# JTAG_Trace.net
KiCad netlist of a schematic drawn in Altium Designer
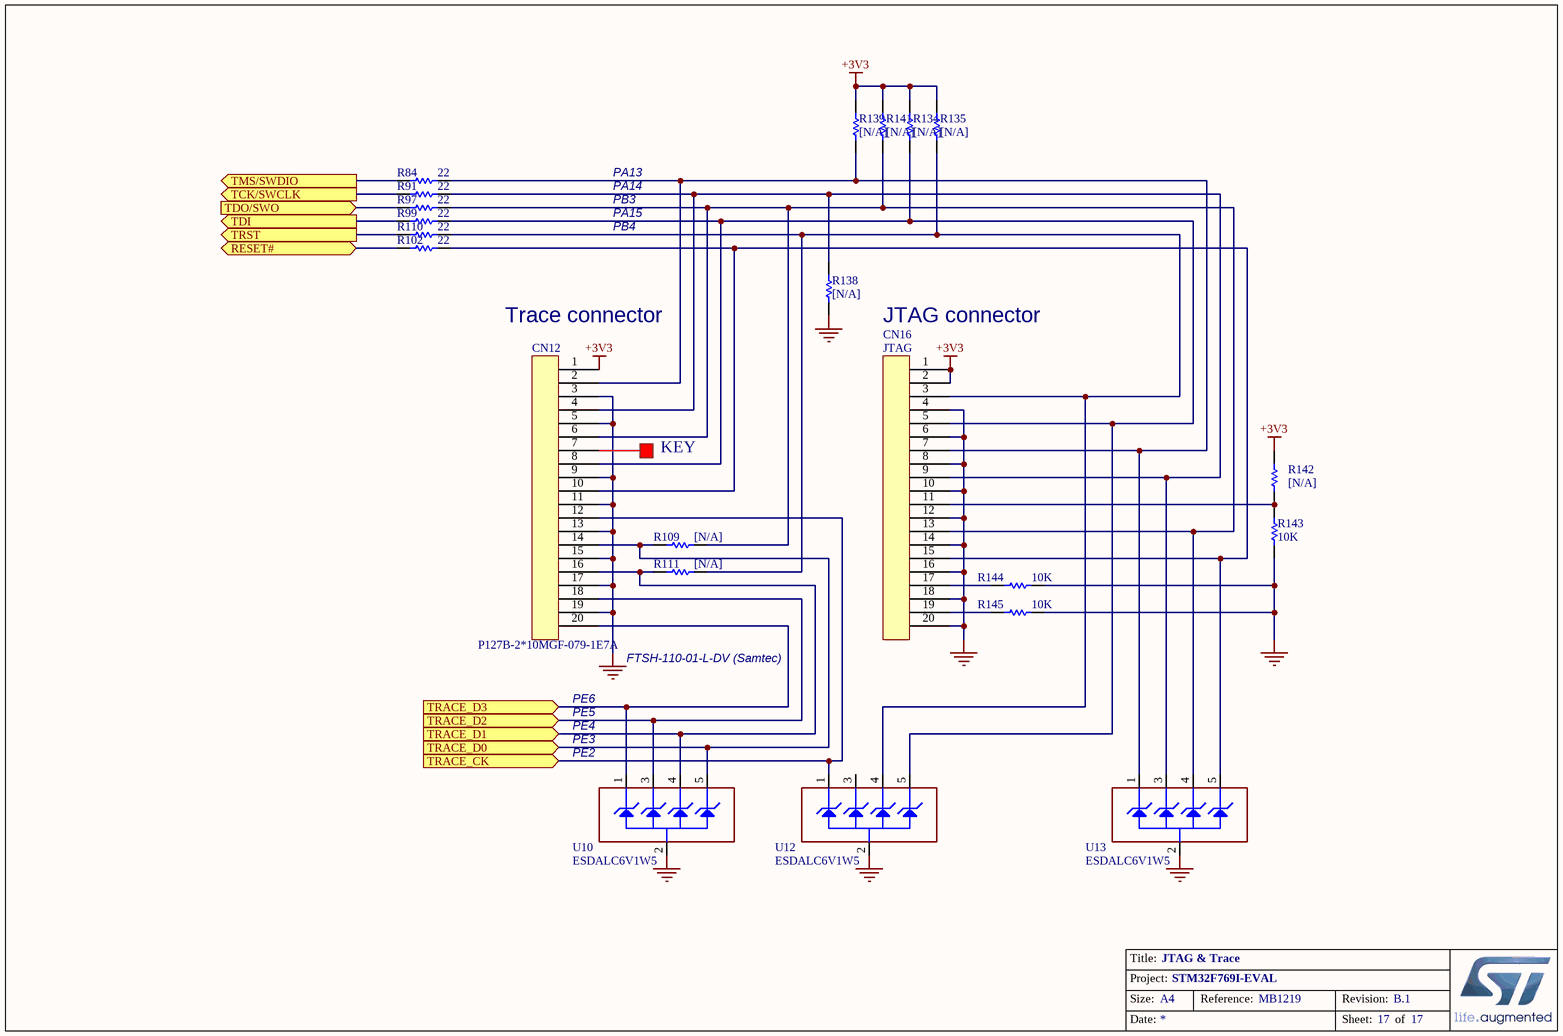
[diagram p0: JTAG&Trace.SchDoc]

(export (version "E")
  (design (tool "Eeschema 10.0.6"))
  (components
    (comp (ref "CN12")
      (value "P127B-2*10MGF-079-1E7A")
      (footprint "FTSH-110-01-L-DV")
      (libsource (lib "*") (part "20PIN1"))
    )
    (comp (ref "CN16") (value "JTAG") (footprint "IDC20S") (libsource (lib "*") (part "20PIN1")))
    (comp (ref "R84")
      (value "22")
      (footprint "0603R")
      (description "Resistor")
      (fields (field (name "PUBLISHER") "Altium Limited"))
      (libsource (lib "Miscellaneous Devices") (part "Res1"))
    )
    (comp (ref "R91")
      (value "22")
      (footprint "0603R")
      (description "Resistor")
      (fields (field (name "PUBLISHER") "Altium Limited"))
      (libsource (lib "Miscellaneous Devices") (part "Res1"))
    )
    (comp (ref "R97")
      (value "22")
      (footprint "0603R")
      (description "Resistor")
      (fields (field (name "PUBLISHER") "Altium Limited"))
      (libsource (lib "Miscellaneous Devices") (part "Res1"))
    )
    (comp (ref "R99")
      (value "22")
      (footprint "0603R")
      (description "Resistor")
      (fields (field (name "PUBLISHER") "Altium Limited"))
      (libsource (lib "Miscellaneous Devices") (part "Res1"))
    )
    (comp (ref "R102")
      (value "22")
      (footprint "0603R")
      (description "Resistor")
      (fields (field (name "PUBLISHER") "Altium Limited"))
      (libsource (lib "Miscellaneous Devices") (part "Res1"))
    )
    (comp (ref "R109")
      (value "[N/A]")
      (footprint "0603R")
      (description "Resistor")
      (fields (field (name "PUBLISHER") "Altium Limited"))
      (libsource (lib "Miscellaneous Devices") (part "Res1"))
    )
    (comp (ref "R110")
      (value "22")
      (footprint "0603R")
      (description "Resistor")
      (fields (field (name "PUBLISHER") "Altium Limited"))
      (libsource (lib "Miscellaneous Devices") (part "Res1"))
    )
    (comp (ref "R111")
      (value "[N/A]")
      (footprint "0603R")
      (description "Resistor")
      (fields (field (name "PUBLISHER") "Altium Limited"))
      (libsource (lib "Miscellaneous Devices") (part "Res1"))
    )
    (comp (ref "R134")
      (value "[N/A]")
      (footprint "0603R")
      (description "Resistor")
      (fields (field (name "PUBLISHER") "Altium Limited"))
      (libsource (lib "Miscellaneous Devices") (part "Res1"))
    )
    (comp (ref "R135")
      (value "[N/A]")
      (footprint "0603R")
      (description "Resistor")
      (fields (field (name "PUBLISHER") "Altium Limited"))
      (libsource (lib "Miscellaneous Devices") (part "Res1"))
    )
    (comp (ref "R138")
      (value "[N/A]")
      (footprint "0603R")
      (description "Resistor")
      (fields (field (name "PUBLISHER") "Altium Limited"))
      (libsource (lib "Miscellaneous Devices") (part "Res1"))
    )
    (comp (ref "R139")
      (value "[N/A]")
      (footprint "0603R")
      (description "Resistor")
      (fields (field (name "PUBLISHER") "Altium Limited"))
      (libsource (lib "Miscellaneous Devices") (part "Res1"))
    )
    (comp (ref "R141")
      (value "[N/A]")
      (footprint "0603R")
      (description "Resistor")
      (fields (field (name "PUBLISHER") "Altium Limited"))
      (libsource (lib "Miscellaneous Devices") (part "Res1"))
    )
    (comp (ref "R142")
      (value "[N/A]")
      (footprint "0603R")
      (description "Resistor")
      (fields (field (name "PUBLISHER") "Altium Limited"))
      (libsource (lib "Miscellaneous Devices") (part "Res1"))
    )
    (comp (ref "R143")
      (value "10K")
      (footprint "0603R")
      (description "Resistor")
      (fields (field (name "PUBLISHER") "Altium Limited"))
      (libsource (lib "Miscellaneous Devices") (part "Res1"))
    )
    (comp (ref "R144")
      (value "10K")
      (footprint "0603R")
      (description "Resistor")
      (fields (field (name "PUBLISHER") "Altium Limited"))
      (libsource (lib "Miscellaneous Devices") (part "Res1"))
    )
    (comp (ref "R145")
      (value "10K")
      (footprint "0603R")
      (description "Resistor")
      (fields (field (name "PUBLISHER") "Altium Limited"))
      (libsource (lib "Miscellaneous Devices") (part "Res1"))
    )
    (comp (ref "U10")
      (value "ESDALC6V1W5")
      (footprint "SOT-353")
      (description "Dual Transil array for ESD protection")
      (libsource (lib "MB1167_1") (part "ESDALC6V1W5"))
    )
    (comp (ref "U12")
      (value "ESDALC6V1W5")
      (footprint "SOT-353")
      (description "Dual Transil array for ESD protection")
      (libsource (lib "MB1167_1") (part "ESDALC6V1W5"))
    )
    (comp (ref "U13")
      (value "ESDALC6V1W5")
      (footprint "SOT-353")
      (description "Dual Transil array for ESD protection")
      (libsource (lib "MB1167_1") (part "ESDALC6V1W5"))
    )
  )
  (nets
    (net (code "1") (name "+3V3") (class "Default")
      (node (ref "CN12") (pin "1") (pintype "passive"))
      (node (ref "CN16") (pin "1") (pintype "passive"))
      (node (ref "CN16") (pin "2") (pintype "passive"))
      (node (ref "R134") (pin "2") (pinfunction "2_2") (pintype "passive"))
      (node (ref "R135") (pin "2") (pinfunction "2_2") (pintype "passive"))
      (node (ref "R139") (pin "2") (pinfunction "2_2") (pintype "passive"))
      (node (ref "R141") (pin "2") (pinfunction "2_2") (pintype "passive"))
      (node (ref "R142") (pin "2") (pinfunction "2_2") (pintype "passive"))
    )
    (net (code "2") (name "/RESET#") (class "Default")
      (node (ref "R102") (pin "2") (pinfunction "2_2") (pintype "passive"))
    )
    (net (code "3") (name "/TCK{slash}SWCLK") (class "Default")
      (node (ref "R91") (pin "2") (pinfunction "2_2") (pintype "passive"))
    )
    (net (code "4") (name "/TDI") (class "Default")
      (node (ref "R99") (pin "2") (pinfunction "2_2") (pintype "passive"))
    )
    (net (code "5") (name "/TDO{slash}SWO") (class "Default")
      (node (ref "R97") (pin "2") (pinfunction "2_2") (pintype "passive"))
    )
    (net (code "6") (name "/TMS{slash}SWDIO") (class "Default")
      (node (ref "R84") (pin "2") (pinfunction "2_2") (pintype "passive"))
    )
    (net (code "7") (name "/TRACE_CK") (class "Default")
      (node (ref "CN12") (pin "12") (pintype "passive"))
      (node (ref "U12") (pin "1") (pinfunction "IO1_1") (pintype "passive"))
    )
    (net (code "8") (name "/TRACE_D0") (class "Default")
      (node (ref "CN12") (pin "14") (pintype "passive"))
      (node (ref "R109") (pin "1") (pinfunction "1_1") (pintype "passive"))
      (node (ref "U10") (pin "5") (pinfunction "IO4_5") (pintype "passive"))
    )
    (net (code "9") (name "/TRACE_D1") (class "Default")
      (node (ref "CN12") (pin "16") (pintype "passive"))
      (node (ref "R111") (pin "1") (pinfunction "1_1") (pintype "passive"))
      (node (ref "U10") (pin "4") (pinfunction "IO3_4") (pintype "passive"))
    )
    (net (code "10") (name "/TRACE_D2") (class "Default")
      (node (ref "CN12") (pin "18") (pintype "passive"))
      (node (ref "U10") (pin "3") (pinfunction "IO2_3") (pintype "passive"))
    )
    (net (code "11") (name "/TRACE_D3") (class "Default")
      (node (ref "CN12") (pin "20") (pintype "passive"))
      (node (ref "U10") (pin "1") (pinfunction "IO1_1") (pintype "passive"))
    )
    (net (code "12") (name "/TRST") (class "Default")
      (node (ref "R110") (pin "2") (pinfunction "2_2") (pintype "passive"))
    )
    (net (code "13") (name "GND") (class "Default")
      (node (ref "CN12") (pin "11") (pintype "passive"))
      (node (ref "CN12") (pin "13") (pintype "passive"))
      (node (ref "CN12") (pin "15") (pintype "passive"))
      (node (ref "CN12") (pin "17") (pintype "passive"))
      (node (ref "CN12") (pin "19") (pintype "passive"))
      (node (ref "CN12") (pin "3") (pintype "passive"))
      (node (ref "CN12") (pin "5") (pintype "passive"))
      (node (ref "CN12") (pin "9") (pintype "passive"))
      (node (ref "CN16") (pin "10") (pintype "passive"))
      (node (ref "CN16") (pin "12") (pintype "passive"))
      (node (ref "CN16") (pin "14") (pintype "passive"))
      (node (ref "CN16") (pin "16") (pintype "passive"))
      (node (ref "CN16") (pin "18") (pintype "passive"))
      (node (ref "CN16") (pin "20") (pintype "passive"))
      (node (ref "CN16") (pin "4") (pintype "passive"))
      (node (ref "CN16") (pin "6") (pintype "passive"))
      (node (ref "CN16") (pin "8") (pintype "passive"))
      (node (ref "R138") (pin "1") (pinfunction "1_1") (pintype "passive"))
      (node (ref "R143") (pin "1") (pinfunction "1_1") (pintype "passive"))
      (node (ref "R144") (pin "1") (pinfunction "1_1") (pintype "passive"))
      (node (ref "R145") (pin "1") (pinfunction "1_1") (pintype "passive"))
      (node (ref "U10") (pin "2") (pinfunction "GND_2") (pintype "passive"))
      (node (ref "U12") (pin "2") (pinfunction "GND_2") (pintype "passive"))
      (node (ref "U13") (pin "2") (pinfunction "GND_2") (pintype "passive"))
    )
    (net (code "14") (name "Net-(CN16-Pad11)") (class "Default")
      (node (ref "CN16") (pin "11") (pintype "passive"))
      (node (ref "R142") (pin "1") (pinfunction "1_1") (pintype "passive"))
      (node (ref "R143") (pin "2") (pinfunction "2_2") (pintype "passive"))
    )
    (net (code "15") (name "Net-(CN16-Pad17)") (class "Default")
      (node (ref "CN16") (pin "17") (pintype "passive"))
      (node (ref "R144") (pin "2") (pinfunction "2_2") (pintype "passive"))
    )
    (net (code "16") (name "Net-(CN16-Pad19)") (class "Default")
      (node (ref "CN16") (pin "19") (pintype "passive"))
      (node (ref "R145") (pin "2") (pinfunction "2_2") (pintype "passive"))
    )
    (net (code "17") (name "Net-(U12-IO3)") (class "Default")
      (node (ref "CN16") (pin "3") (pintype "passive"))
      (node (ref "R110") (pin "1") (pinfunction "1_1") (pintype "passive"))
      (node (ref "R111") (pin "2") (pinfunction "2_2") (pintype "passive"))
      (node (ref "R135") (pin "1") (pinfunction "1_1") (pintype "passive"))
      (node (ref "U12") (pin "4") (pinfunction "IO3_4") (pintype "passive"))
    )
    (net (code "18") (name "Net-(U12-IO4)") (class "Default")
      (node (ref "CN12") (pin "8") (pintype "passive"))
      (node (ref "CN16") (pin "5") (pintype "passive"))
      (node (ref "R134") (pin "1") (pinfunction "1_1") (pintype "passive"))
      (node (ref "R99") (pin "1") (pinfunction "1_1") (pintype "passive"))
      (node (ref "U12") (pin "5") (pinfunction "IO4_5") (pintype "passive"))
    )
    (net (code "19") (name "Net-(U13-IO1)") (class "Default")
      (node (ref "CN12") (pin "2") (pintype "passive"))
      (node (ref "CN16") (pin "7") (pintype "passive"))
      (node (ref "R139") (pin "1") (pinfunction "1_1") (pintype "passive"))
      (node (ref "R84") (pin "1") (pinfunction "1_1") (pintype "passive"))
      (node (ref "U13") (pin "1") (pinfunction "IO1_1") (pintype "passive"))
    )
    (net (code "20") (name "Net-(U13-IO2)") (class "Default")
      (node (ref "CN12") (pin "4") (pintype "passive"))
      (node (ref "CN16") (pin "9") (pintype "passive"))
      (node (ref "R138") (pin "2") (pinfunction "2_2") (pintype "passive"))
      (node (ref "R91") (pin "1") (pinfunction "1_1") (pintype "passive"))
      (node (ref "U13") (pin "3") (pinfunction "IO2_3") (pintype "passive"))
    )
    (net (code "21") (name "Net-(U13-IO3)") (class "Default")
      (node (ref "CN12") (pin "6") (pintype "passive"))
      (node (ref "CN16") (pin "13") (pintype "passive"))
      (node (ref "R109") (pin "2") (pinfunction "2_2") (pintype "passive"))
      (node (ref "R141") (pin "1") (pinfunction "1_1") (pintype "passive"))
      (node (ref "R97") (pin "1") (pinfunction "1_1") (pintype "passive"))
      (node (ref "U13") (pin "4") (pinfunction "IO3_4") (pintype "passive"))
    )
    (net (code "22") (name "Net-(U13-IO4)") (class "Default")
      (node (ref "CN12") (pin "10") (pintype "passive"))
      (node (ref "CN16") (pin "15") (pintype "passive"))
      (node (ref "R102") (pin "1") (pinfunction "1_1") (pintype "passive"))
      (node (ref "U13") (pin "5") (pinfunction "IO4_5") (pintype "passive"))
    )
    (net (code "23") (name "unconnected-(CN12-Pad7)") (class "Default")
      (node (ref "CN12") (pin "7") (pintype "passive"))
    )
    (net (code "24") (name "unconnected-(U12-IO2-Pad3)") (class "Default")
      (node (ref "U12") (pin "3") (pinfunction "IO2_3") (pintype "passive"))
    )
  )
)
